# 08_Peripherals.net
KiCad netlist of a schematic drawn in Altium Designer
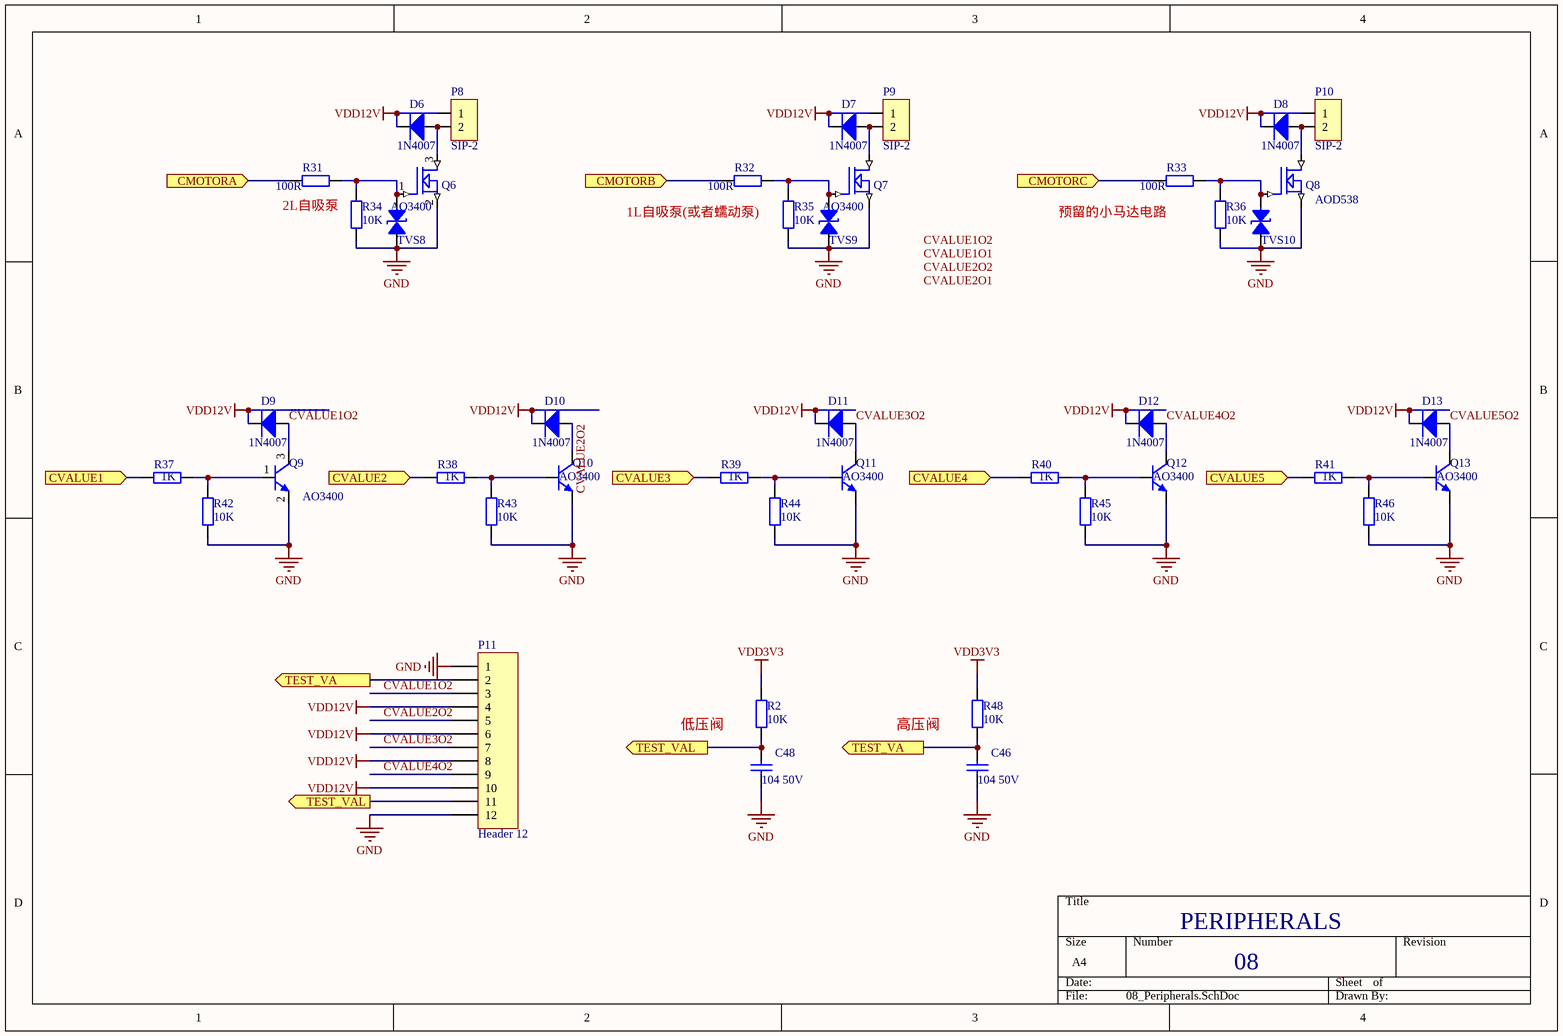
[diagram p0: 08_Peripherals.SchDoc]

(export (version "E")
  (design (tool "Eeschema 10.0.6"))
  (components
    (comp (ref "C46")
      (value "104 50V")
      (footprint "SMD-0603C")
      (description "贴片电容 10%")
      (libsource (lib "XiaoyI") (part "CAP4"))
    )
    (comp (ref "C48")
      (value "104 50V")
      (footprint "PCB1:SMD-0603C")
      (description "贴片电容 10%")
      (libsource (lib "XiaoyI") (part "CAP4"))
    )
    (comp (ref "D6")
      (value "1N4007")
      (footprint "DO-214-AC")
      (description "贴片二极管")
      (libsource (lib "XiaoyI") (part "DIODE2"))
    )
    (comp (ref "D7")
      (value "1N4007")
      (footprint "DO-214-AC")
      (description "贴片二极管")
      (libsource (lib "XiaoyI") (part "DIODE2"))
    )
    (comp (ref "D8")
      (value "1N4007")
      (footprint "DO-214-AC")
      (description "贴片二极管")
      (libsource (lib "XiaoyI") (part "DIODE2"))
    )
    (comp (ref "D9")
      (value "1N4007")
      (footprint "DO-214-AC")
      (description "贴片二极管")
      (libsource (lib "XiaoyI") (part "DIODE2"))
    )
    (comp (ref "D10")
      (value "1N4007")
      (footprint "DO-214-AC")
      (description "贴片二极管")
      (libsource (lib "XiaoyI") (part "DIODE2"))
    )
    (comp (ref "D11")
      (value "1N4007")
      (footprint "DO-214-AC")
      (description "贴片二极管")
      (libsource (lib "XiaoyI") (part "DIODE2"))
    )
    (comp (ref "D12")
      (value "1N4007")
      (footprint "DO-214-AC")
      (description "贴片二极管")
      (libsource (lib "XiaoyI") (part "DIODE2"))
    )
    (comp (ref "D13")
      (value "1N4007")
      (footprint "DO-214-AC")
      (description "贴片二极管")
      (libsource (lib "XiaoyI") (part "DIODE2"))
    )
    (comp (ref "P8")
      (value "SIP-2")
      (footprint "SIP-2A")
      (description "XH2.54 2P 立贴")
      (libsource (lib "XiaoyI") (part "SIP-2"))
    )
    (comp (ref "P9")
      (value "SIP-2")
      (footprint "SIP-2A")
      (description "XH2.54 2P 立贴")
      (libsource (lib "XiaoyI") (part "SIP-2"))
    )
    (comp (ref "P10")
      (value "SIP-2")
      (footprint "VH-AW-3.96*2P")
      (description "XH2.54 2P 立贴")
      (libsource (lib "XiaoyI") (part "SIP-2"))
    )
    (comp (ref "P11")
      (value "Header 12")
      (footprint "12X2.54MMZ")
      (description "Header, 12-Pin")
      (fields (field (name "PUBLISHER") "Altium Limited"))
      (libsource (lib "Miscellaneous Connectors") (part "Header 12"))
    )
    (comp (ref "Q6")
      (value "AO3400")
      (footprint "SOT-23")
      (description "MOSFET N")
      (libsource (lib "") (part "MOSFET N_1"))
    )
    (comp (ref "Q7")
      (value "AO3400")
      (footprint "SOT-23")
      (description "MOSFET N")
      (libsource (lib "XiaoyI") (part "MOSFET N"))
    )
    (comp (ref "Q8")
      (value "AOD538")
      (footprint "TO252")
      (description "MOSFET N")
      (libsource (lib "XiaoyI") (part "MOSFET N"))
    )
    (comp (ref "Q9")
      (value "AO3400")
      (footprint "SOT-23")
      (description "三极管")
      (libsource (lib "") (part "NPN-1_1"))
    )
    (comp (ref "Q10")
      (value "AO3400")
      (footprint "SOT-23")
      (description "三极管")
      (libsource (lib "XiaoyI") (part "NPN-1"))
    )
    (comp (ref "Q11")
      (value "AO3400")
      (footprint "SOT-23")
      (description "三极管")
      (libsource (lib "XiaoyI") (part "NPN-1"))
    )
    (comp (ref "Q12")
      (value "AO3400")
      (footprint "SOT-23")
      (description "三极管")
      (libsource (lib "XiaoyI") (part "NPN-1"))
    )
    (comp (ref "Q13")
      (value "AO3400")
      (footprint "SOT-23")
      (description "三极管")
      (libsource (lib "XiaoyI") (part "NPN-1"))
    )
    (comp (ref "R2")
      (value "10K")
      (footprint "PCB1:SMD-0603")
      (description "贴片电阻 5%")
      (libsource (lib "") (part "RES-SOP_2"))
    )
    (comp (ref "R31")
      (value "100R")
      (footprint "SMD-0603")
      (description "贴片电阻 5%")
      (libsource (lib "") (part "RES-SOP_1"))
    )
    (comp (ref "R32")
      (value "100R")
      (footprint "SMD-0603")
      (description "贴片电阻 5%")
      (libsource (lib "") (part "RES-SOP_1"))
    )
    (comp (ref "R33")
      (value "100R")
      (footprint "SMD-0603")
      (description "贴片电阻 5%")
      (libsource (lib "") (part "RES-SOP_1"))
    )
    (comp (ref "R34")
      (value "10K")
      (footprint "SMD-0603")
      (description "贴片电阻 5%")
      (libsource (lib "XiaoyI") (part "RES-SOP"))
    )
    (comp (ref "R35")
      (value "10K")
      (footprint "SMD-0603")
      (description "贴片电阻 5%")
      (libsource (lib "XiaoyI") (part "RES-SOP"))
    )
    (comp (ref "R36")
      (value "10K")
      (footprint "SMD-0603")
      (description "贴片电阻 5%")
      (libsource (lib "XiaoyI") (part "RES-SOP"))
    )
    (comp (ref "R37")
      (value "1K")
      (footprint "SMD-0603")
      (description "贴片电阻 5%")
      (libsource (lib "") (part "RES-SOP_1"))
    )
    (comp (ref "R38")
      (value "1K")
      (footprint "SMD-0603")
      (description "贴片电阻 5%")
      (libsource (lib "") (part "RES-SOP_1"))
    )
    (comp (ref "R39")
      (value "1K")
      (footprint "SMD-0603")
      (description "贴片电阻 5%")
      (libsource (lib "") (part "RES-SOP_1"))
    )
    (comp (ref "R40")
      (value "1K")
      (footprint "SMD-0603")
      (description "贴片电阻 5%")
      (libsource (lib "") (part "RES-SOP_1"))
    )
    (comp (ref "R41")
      (value "1K")
      (footprint "SMD-0603")
      (description "贴片电阻 5%")
      (libsource (lib "") (part "RES-SOP_1"))
    )
    (comp (ref "R42")
      (value "10K")
      (footprint "SMD-0603")
      (description "贴片电阻 5%")
      (libsource (lib "XiaoyI") (part "RES-SOP"))
    )
    (comp (ref "R43")
      (value "10K")
      (footprint "SMD-0603")
      (description "贴片电阻 5%")
      (libsource (lib "XiaoyI") (part "RES-SOP"))
    )
    (comp (ref "R44")
      (value "10K")
      (footprint "SMD-0603")
      (description "贴片电阻 5%")
      (libsource (lib "XiaoyI") (part "RES-SOP"))
    )
    (comp (ref "R45")
      (value "10K")
      (footprint "SMD-0603")
      (description "贴片电阻 5%")
      (libsource (lib "XiaoyI") (part "RES-SOP"))
    )
    (comp (ref "R46")
      (value "10K")
      (footprint "SMD-0603")
      (description "贴片电阻 5%")
      (libsource (lib "XiaoyI") (part "RES-SOP"))
    )
    (comp (ref "R48")
      (value "10K")
      (footprint "SMD-0603")
      (description "贴片电阻 5%")
      (libsource (lib "") (part "RES-SOP_2"))
    )
    (comp (ref "TVS8")
      (value "ESD5Z5.0CT1G")
      (footprint "SOD-523")
      (description "TVS")
      (libsource (lib "XiaoyI") (part "TVS-1"))
    )
    (comp (ref "TVS9")
      (value "ESD5Z5.0CT1G")
      (footprint "SOD-523")
      (description "TVS")
      (libsource (lib "XiaoyI") (part "TVS-1"))
    )
    (comp (ref "TVS10")
      (value "ESD5Z5.0CT1G")
      (footprint "SOD-523")
      (description "TVS")
      (libsource (lib "XiaoyI") (part "TVS-1"))
    )
  )
  (nets
    (net (code "1") (name "/CMOTORA") (class "Default")
      (node (ref "R31") (pin "2") (pinfunction "2_2") (pintype "passive"))
    )
    (net (code "2") (name "/CMOTORB") (class "Default")
      (node (ref "R32") (pin "2") (pinfunction "2_2") (pintype "passive"))
    )
    (net (code "3") (name "/CMOTORC") (class "Default")
      (node (ref "R33") (pin "2") (pinfunction "2_2") (pintype "passive"))
    )
    (net (code "4") (name "/CVALUE1") (class "Default")
      (node (ref "R37") (pin "2") (pinfunction "2_2") (pintype "passive"))
    )
    (net (code "6") (name "/CVALUE1O2") (class "Default")
      (node (ref "D9") (pin "1") (pinfunction "A_1") (pintype "passive"))
      (node (ref "P11") (pin "3") (pinfunction "3_3") (pintype "passive"))
      (node (ref "Q9") (pin "3") (pinfunction "C_3") (pintype "passive"))
    )
    (net (code "7") (name "/CVALUE2") (class "Default")
      (node (ref "R38") (pin "2") (pinfunction "2_2") (pintype "passive"))
    )
    (net (code "9") (name "/CVALUE2O2") (class "Default")
      (node (ref "D10") (pin "1") (pinfunction "A_1") (pintype "passive"))
      (node (ref "P11") (pin "5") (pinfunction "5_5") (pintype "passive"))
      (node (ref "Q10") (pin "3") (pinfunction "C_3") (pintype "passive"))
    )
    (net (code "10") (name "/CVALUE3") (class "Default")
      (node (ref "R39") (pin "2") (pinfunction "2_2") (pintype "passive"))
    )
    (net (code "11") (name "/CVALUE3O2") (class "Default")
      (node (ref "D11") (pin "1") (pinfunction "A_1") (pintype "passive"))
      (node (ref "P11") (pin "7") (pinfunction "7_7") (pintype "passive"))
      (node (ref "Q11") (pin "3") (pinfunction "C_3") (pintype "passive"))
    )
    (net (code "12") (name "/CVALUE4") (class "Default")
      (node (ref "R40") (pin "2") (pinfunction "2_2") (pintype "passive"))
    )
    (net (code "13") (name "/CVALUE4O2") (class "Default")
      (node (ref "D12") (pin "1") (pinfunction "A_1") (pintype "passive"))
      (node (ref "P11") (pin "9") (pinfunction "9_9") (pintype "passive"))
      (node (ref "Q12") (pin "3") (pinfunction "C_3") (pintype "passive"))
    )
    (net (code "14") (name "/CVALUE5") (class "Default")
      (node (ref "R41") (pin "2") (pinfunction "2_2") (pintype "passive"))
    )
    (net (code "15") (name "/CVALUE5O2") (class "Default")
      (node (ref "D13") (pin "1") (pinfunction "A_1") (pintype "passive"))
      (node (ref "Q13") (pin "3") (pinfunction "C_3") (pintype "passive"))
    )
    (net (code "16") (name "/TEST_VA") (class "Default")
      (node (ref "C46") (pin "2") (pinfunction "2_2") (pintype "passive"))
      (node (ref "P11") (pin "2") (pinfunction "2_2") (pintype "passive"))
      (node (ref "R48") (pin "1") (pinfunction "1_1") (pintype "passive"))
    )
    (net (code "17") (name "/TEST_VAL") (class "Default")
      (node (ref "C48") (pin "2") (pinfunction "2_2") (pintype "passive"))
      (node (ref "P11") (pin "11") (pinfunction "11_11") (pintype "passive"))
      (node (ref "R2") (pin "1") (pinfunction "1_1") (pintype "passive"))
    )
    (net (code "18") (name "GND") (class "Default")
      (node (ref "C46") (pin "1") (pinfunction "1_1") (pintype "passive"))
      (node (ref "C48") (pin "1") (pinfunction "1_1") (pintype "passive"))
      (node (ref "P11") (pin "1") (pinfunction "1_1") (pintype "passive"))
      (node (ref "P11") (pin "12") (pinfunction "12_12") (pintype "passive"))
      (node (ref "Q10") (pin "2") (pinfunction "E_2") (pintype "passive"))
      (node (ref "Q11") (pin "2") (pinfunction "E_2") (pintype "passive"))
      (node (ref "Q12") (pin "2") (pinfunction "E_2") (pintype "passive"))
      (node (ref "Q13") (pin "2") (pinfunction "E_2") (pintype "passive"))
      (node (ref "Q6") (pin "2") (pinfunction "S_2") (pintype "output"))
      (node (ref "Q7") (pin "2") (pinfunction "S_2") (pintype "output"))
      (node (ref "Q8") (pin "2") (pinfunction "S_2") (pintype "output"))
      (node (ref "Q9") (pin "2") (pinfunction "E_2") (pintype "passive"))
      (node (ref "R34") (pin "2") (pinfunction "2_2") (pintype "passive"))
      (node (ref "R35") (pin "2") (pinfunction "2_2") (pintype "passive"))
      (node (ref "R36") (pin "2") (pinfunction "2_2") (pintype "passive"))
      (node (ref "R42") (pin "2") (pinfunction "2_2") (pintype "passive"))
      (node (ref "R43") (pin "2") (pinfunction "2_2") (pintype "passive"))
      (node (ref "R44") (pin "2") (pinfunction "2_2") (pintype "passive"))
      (node (ref "R45") (pin "2") (pinfunction "2_2") (pintype "passive"))
      (node (ref "R46") (pin "2") (pinfunction "2_2") (pintype "passive"))
      (node (ref "TVS10") (pin "1") (pinfunction "A_1") (pintype "passive"))
      (node (ref "TVS8") (pin "1") (pinfunction "A_1") (pintype "passive"))
      (node (ref "TVS9") (pin "1") (pinfunction "A_1") (pintype "passive"))
    )
    (net (code "19") (name "Net-(D6-A)") (class "Default")
      (node (ref "D6") (pin "1") (pinfunction "A_1") (pintype "passive"))
      (node (ref "P8") (pin "2") (pinfunction "2_2") (pintype "passive"))
      (node (ref "Q6") (pin "3") (pinfunction "D_3") (pintype "input"))
    )
    (net (code "20") (name "Net-(D7-A)") (class "Default")
      (node (ref "D7") (pin "1") (pinfunction "A_1") (pintype "passive"))
      (node (ref "P9") (pin "2") (pinfunction "2_2") (pintype "passive"))
      (node (ref "Q7") (pin "3") (pinfunction "D_3") (pintype "input"))
    )
    (net (code "21") (name "Net-(D8-A)") (class "Default")
      (node (ref "D8") (pin "1") (pinfunction "A_1") (pintype "passive"))
      (node (ref "P10") (pin "2") (pinfunction "2_2") (pintype "passive"))
      (node (ref "Q8") (pin "3") (pinfunction "D_3") (pintype "input"))
    )
    (net (code "22") (name "Net-(Q6-G)") (class "Default")
      (node (ref "Q6") (pin "1") (pinfunction "G_1") (pintype "input"))
      (node (ref "R31") (pin "1") (pinfunction "1_1") (pintype "passive"))
      (node (ref "R34") (pin "1") (pinfunction "1_1") (pintype "passive"))
      (node (ref "TVS8") (pin "2") (pinfunction "B_2") (pintype "passive"))
    )
    (net (code "23") (name "Net-(Q7-G)") (class "Default")
      (node (ref "Q7") (pin "1") (pinfunction "G_1") (pintype "input"))
      (node (ref "R32") (pin "1") (pinfunction "1_1") (pintype "passive"))
      (node (ref "R35") (pin "1") (pinfunction "1_1") (pintype "passive"))
      (node (ref "TVS9") (pin "2") (pinfunction "B_2") (pintype "passive"))
    )
    (net (code "24") (name "Net-(Q8-G)") (class "Default")
      (node (ref "Q8") (pin "1") (pinfunction "G_1") (pintype "input"))
      (node (ref "R33") (pin "1") (pinfunction "1_1") (pintype "passive"))
      (node (ref "R36") (pin "1") (pinfunction "1_1") (pintype "passive"))
      (node (ref "TVS10") (pin "2") (pinfunction "B_2") (pintype "passive"))
    )
    (net (code "25") (name "Net-(Q9-B)") (class "Default")
      (node (ref "Q9") (pin "1") (pinfunction "B_1") (pintype "passive"))
      (node (ref "R37") (pin "1") (pinfunction "1_1") (pintype "passive"))
      (node (ref "R42") (pin "1") (pinfunction "1_1") (pintype "passive"))
    )
    (net (code "26") (name "Net-(Q10-B)") (class "Default")
      (node (ref "Q10") (pin "1") (pinfunction "B_1") (pintype "passive"))
      (node (ref "R38") (pin "1") (pinfunction "1_1") (pintype "passive"))
      (node (ref "R43") (pin "1") (pinfunction "1_1") (pintype "passive"))
    )
    (net (code "27") (name "Net-(Q11-B)") (class "Default")
      (node (ref "Q11") (pin "1") (pinfunction "B_1") (pintype "passive"))
      (node (ref "R39") (pin "1") (pinfunction "1_1") (pintype "passive"))
      (node (ref "R44") (pin "1") (pinfunction "1_1") (pintype "passive"))
    )
    (net (code "28") (name "Net-(Q12-B)") (class "Default")
      (node (ref "Q12") (pin "1") (pinfunction "B_1") (pintype "passive"))
      (node (ref "R40") (pin "1") (pinfunction "1_1") (pintype "passive"))
      (node (ref "R45") (pin "1") (pinfunction "1_1") (pintype "passive"))
    )
    (net (code "29") (name "Net-(Q13-B)") (class "Default")
      (node (ref "Q13") (pin "1") (pinfunction "B_1") (pintype "passive"))
      (node (ref "R41") (pin "1") (pinfunction "1_1") (pintype "passive"))
      (node (ref "R46") (pin "1") (pinfunction "1_1") (pintype "passive"))
    )
    (net (code "30") (name "VDD3V3") (class "Default")
      (node (ref "R2") (pin "2") (pinfunction "2_2") (pintype "passive"))
      (node (ref "R48") (pin "2") (pinfunction "2_2") (pintype "passive"))
    )
    (net (code "31") (name "VDD12V") (class "Default")
      (node (ref "D10") (pin "2") (pinfunction "K_2") (pintype "passive"))
      (node (ref "D11") (pin "2") (pinfunction "K_2") (pintype "passive"))
      (node (ref "D12") (pin "2") (pinfunction "K_2") (pintype "passive"))
      (node (ref "D13") (pin "2") (pinfunction "K_2") (pintype "passive"))
      (node (ref "D6") (pin "2") (pinfunction "K_2") (pintype "passive"))
      (node (ref "D7") (pin "2") (pinfunction "K_2") (pintype "passive"))
      (node (ref "D8") (pin "2") (pinfunction "K_2") (pintype "passive"))
      (node (ref "D9") (pin "2") (pinfunction "K_2") (pintype "passive"))
      (node (ref "P10") (pin "1") (pinfunction "1_1") (pintype "passive"))
      (node (ref "P11") (pin "10") (pinfunction "10_10") (pintype "passive"))
      (node (ref "P11") (pin "4") (pinfunction "4_4") (pintype "passive"))
      (node (ref "P11") (pin "6") (pinfunction "6_6") (pintype "passive"))
      (node (ref "P11") (pin "8") (pinfunction "8_8") (pintype "passive"))
      (node (ref "P8") (pin "1") (pinfunction "1_1") (pintype "passive"))
      (node (ref "P9") (pin "1") (pinfunction "1_1") (pintype "passive"))
    )
  )
)
